# tiva-c.net
KiCad netlist of a schematic drawn in EAGLE
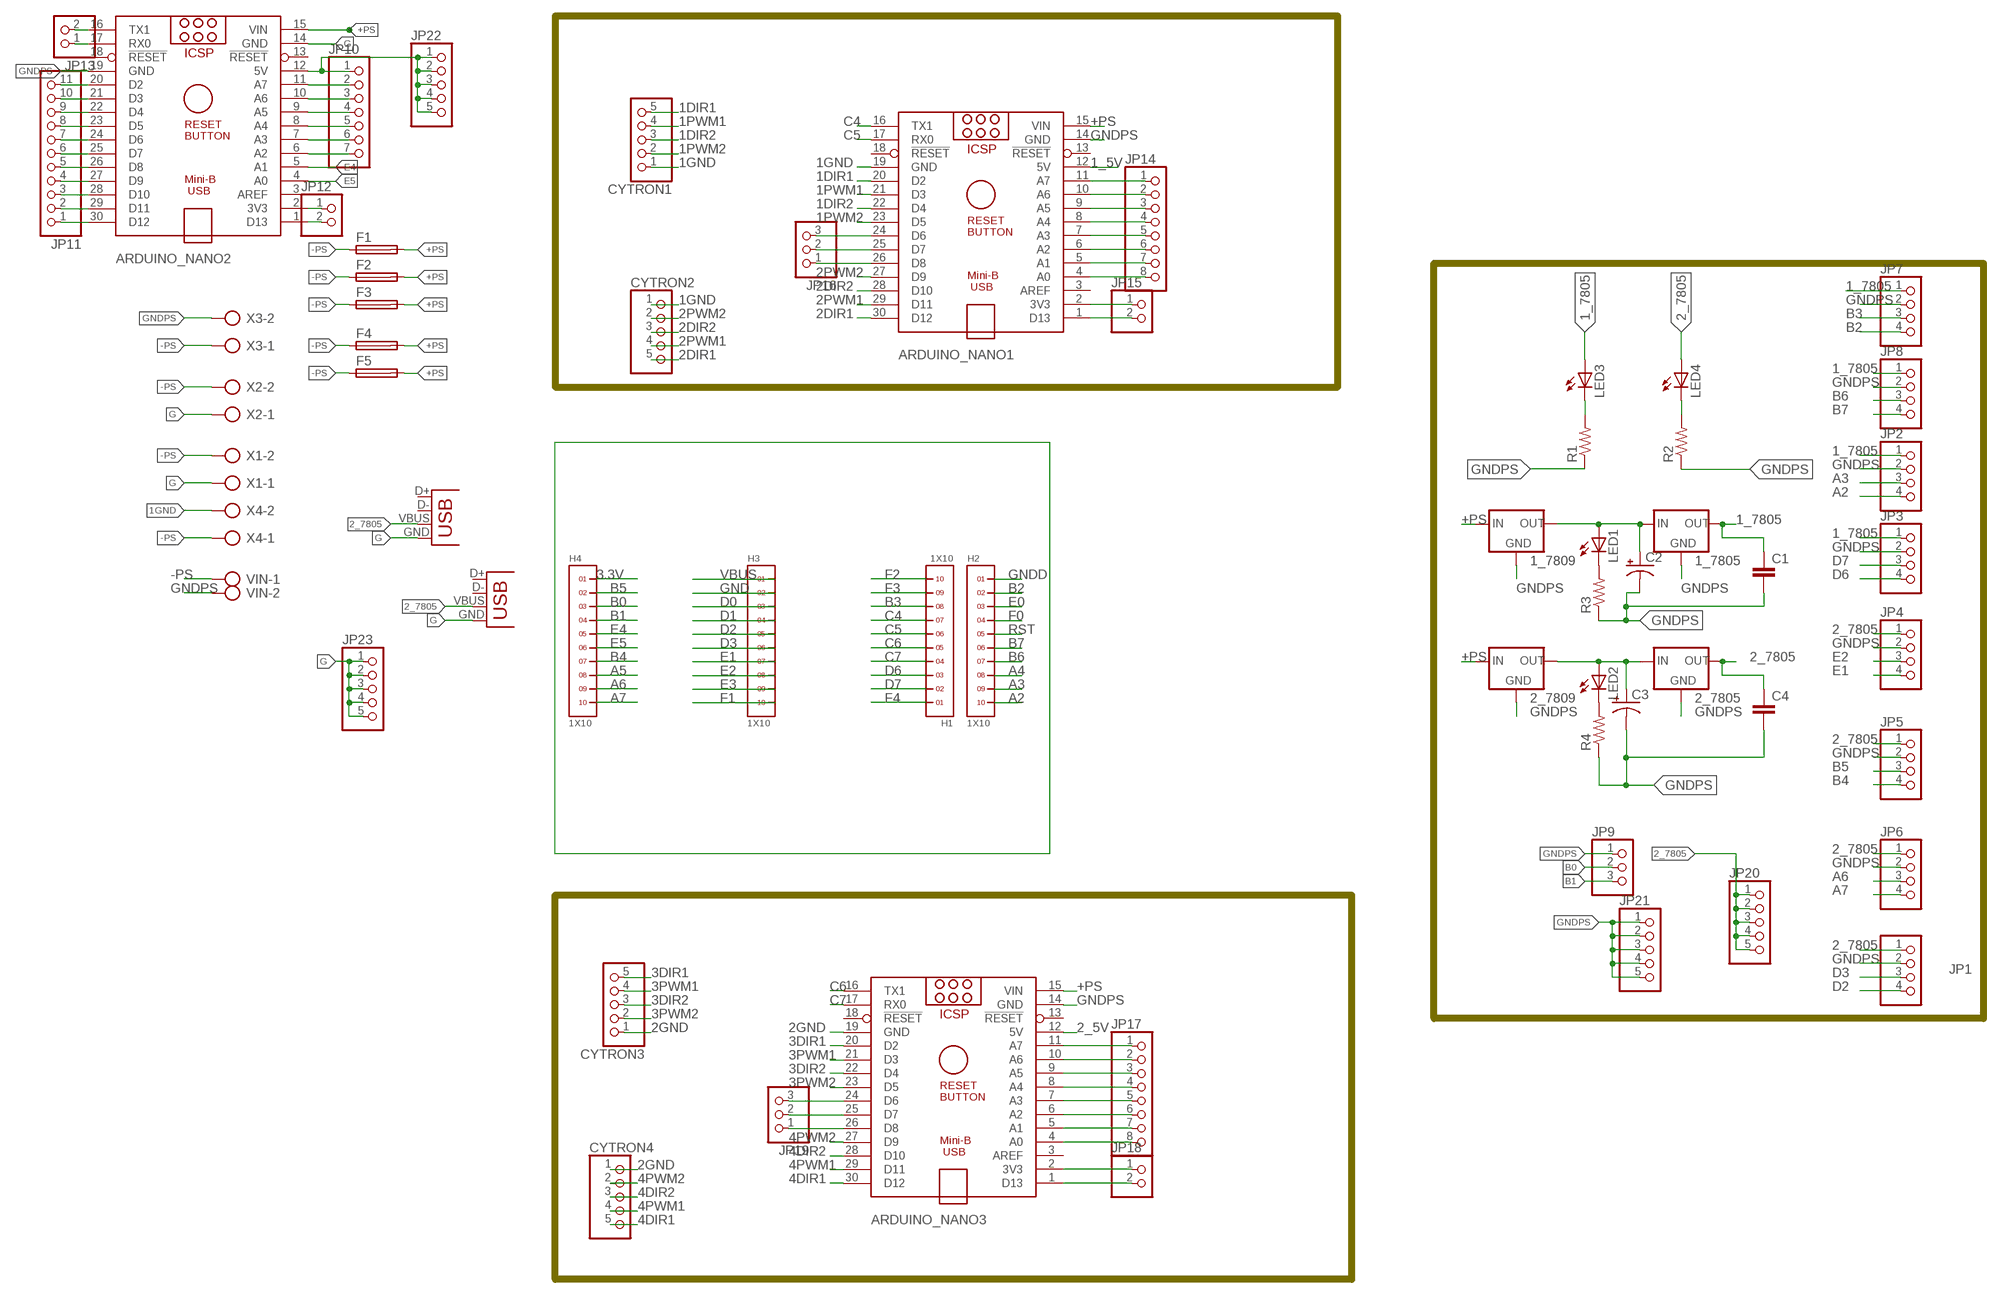
[diagram p0: schematic, sheet 1]

(export (version "E")
  (design (tool "Eeschema 10.0.6"))
  (components
    (comp (ref "1_7805")
      (value "78XXS")
      (footprint "eagle-import:78XXS")
      (libsource (lib "eagle-import") (part "78XXS"))
    )
    (comp (ref "1_7809")
      (value "78XXS")
      (footprint "eagle-import:78XXS")
      (libsource (lib "eagle-import") (part "78XXS"))
    )
    (comp (ref "2_7805")
      (value "78XXS")
      (footprint "eagle-import:78XXS")
      (libsource (lib "eagle-import") (part "78XXS"))
    )
    (comp (ref "2_7809")
      (value "78XXS")
      (footprint "eagle-import:78XXS")
      (libsource (lib "eagle-import") (part "78XXS"))
    )
    (comp (ref "ARDUINO_NANO1")
      (value "ARDUINO_NANO")
      (footprint "eagle-import:ARDUINO_NANO")
      (libsource (lib "eagle-import") (part "ARDUINO_NANO"))
    )
    (comp (ref "ARDUINO_NANO2")
      (value "ARDUINO_NANO")
      (footprint "eagle-import:ARDUINO_NANO")
      (libsource (lib "eagle-import") (part "ARDUINO_NANO"))
    )
    (comp (ref "ARDUINO_NANO3")
      (value "ARDUINO_NANO")
      (footprint "eagle-import:ARDUINO_NANO")
      (libsource (lib "eagle-import") (part "ARDUINO_NANO"))
    )
    (comp (ref "C1")
      (value "C-EU025-030X050")
      (footprint "eagle-import:C025-030X050")
      (libsource (lib "eagle-import") (part "C-EU025-030X050"))
    )
    (comp (ref "C2")
      (value "CPOL-USE2.5-5")
      (footprint "eagle-import:E2,5-5")
      (libsource (lib "eagle-import") (part "CPOL-USE2.5-5"))
    )
    (comp (ref "C3")
      (value "CPOL-USE2.5-5")
      (footprint "eagle-import:E2,5-5")
      (libsource (lib "eagle-import") (part "CPOL-USE2.5-5"))
    )
    (comp (ref "C4")
      (value "C-EU025-030X050")
      (footprint "eagle-import:C025-030X050")
      (libsource (lib "eagle-import") (part "C-EU025-030X050"))
    )
    (comp (ref "CYTRON1")
      (value "PINHD-1X5")
      (footprint "eagle-import:1X05")
      (libsource (lib "eagle-import") (part "PINHD-1X5"))
    )
    (comp (ref "CYTRON2")
      (value "PINHD-1X5")
      (footprint "eagle-import:1X05")
      (libsource (lib "eagle-import") (part "PINHD-1X5"))
    )
    (comp (ref "CYTRON3")
      (value "PINHD-1X5")
      (footprint "eagle-import:1X05")
      (libsource (lib "eagle-import") (part "PINHD-1X5"))
    )
    (comp (ref "CYTRON4")
      (value "PINHD-1X5")
      (footprint "eagle-import:1X05")
      (libsource (lib "eagle-import") (part "PINHD-1X5"))
    )
    (comp (ref "F1")
      (value "SH22,5A")
      (footprint "eagle-import:SH22,5A")
      (fields (field (name "MPN") "0031.7701.11"))
      (libsource (lib "eagle-import") (part "SH22,5A"))
    )
    (comp (ref "F2")
      (value "SH22,5A")
      (footprint "eagle-import:SH22,5A")
      (fields (field (name "MPN") "0031.7701.11"))
      (libsource (lib "eagle-import") (part "SH22,5A"))
    )
    (comp (ref "F3")
      (value "SH22,5A")
      (footprint "eagle-import:SH22,5A")
      (fields (field (name "MPN") "0031.7701.11"))
      (libsource (lib "eagle-import") (part "SH22,5A"))
    )
    (comp (ref "F4")
      (value "SH22,5A")
      (footprint "eagle-import:SH22,5A")
      (fields (field (name "MPN") "0031.7701.11"))
      (libsource (lib "eagle-import") (part "SH22,5A"))
    )
    (comp (ref "F5")
      (value "SH22,5A")
      (footprint "eagle-import:SH22,5A")
      (fields (field (name "MPN") "0031.7701.11"))
      (libsource (lib "eagle-import") (part "SH22,5A"))
    )
    (comp (ref "H1")
      (value "1X10")
      (footprint "eagle-import:1X10")
      (libsource (lib "eagle-import") (part "1X10"))
    )
    (comp (ref "H2")
      (value "1X10")
      (footprint "eagle-import:1X10")
      (libsource (lib "eagle-import") (part "1X10"))
    )
    (comp (ref "H3")
      (value "1X10")
      (footprint "eagle-import:1X10")
      (libsource (lib "eagle-import") (part "1X10"))
    )
    (comp (ref "H4")
      (value "1X10")
      (footprint "eagle-import:1X10")
      (libsource (lib "eagle-import") (part "1X10"))
    )
    (comp (ref "JP1")
      (value "PINHD-1X4")
      (footprint "eagle-import:1X04")
      (libsource (lib "eagle-import") (part "PINHD-1X4"))
    )
    (comp (ref "JP2")
      (value "PINHD-1X4")
      (footprint "eagle-import:1X04")
      (libsource (lib "eagle-import") (part "PINHD-1X4"))
    )
    (comp (ref "JP3")
      (value "PINHD-1X4")
      (footprint "eagle-import:1X04")
      (libsource (lib "eagle-import") (part "PINHD-1X4"))
    )
    (comp (ref "JP4")
      (value "PINHD-1X4")
      (footprint "eagle-import:1X04")
      (libsource (lib "eagle-import") (part "PINHD-1X4"))
    )
    (comp (ref "JP5")
      (value "PINHD-1X4")
      (footprint "eagle-import:1X04")
      (libsource (lib "eagle-import") (part "PINHD-1X4"))
    )
    (comp (ref "JP6")
      (value "PINHD-1X4")
      (footprint "eagle-import:1X04")
      (libsource (lib "eagle-import") (part "PINHD-1X4"))
    )
    (comp (ref "JP7")
      (value "PINHD-1X4")
      (footprint "eagle-import:1X04")
      (libsource (lib "eagle-import") (part "PINHD-1X4"))
    )
    (comp (ref "JP8")
      (value "PINHD-1X4")
      (footprint "eagle-import:1X04")
      (libsource (lib "eagle-import") (part "PINHD-1X4"))
    )
    (comp (ref "JP9")
      (value "PINHD-1X3")
      (footprint "eagle-import:1X03")
      (libsource (lib "eagle-import") (part "PINHD-1X3"))
    )
    (comp (ref "JP10")
      (value "PINHD-1X7")
      (footprint "eagle-import:1X07")
      (libsource (lib "eagle-import") (part "PINHD-1X7"))
    )
    (comp (ref "JP11")
      (value "PINHD-1X11")
      (footprint "eagle-import:1X11")
      (libsource (lib "eagle-import") (part "PINHD-1X11"))
    )
    (comp (ref "JP12")
      (value "PINHD-1X2")
      (footprint "eagle-import:1X02")
      (libsource (lib "eagle-import") (part "PINHD-1X2"))
    )
    (comp (ref "JP13")
      (value "PINHD-1X2")
      (footprint "eagle-import:1X02")
      (libsource (lib "eagle-import") (part "PINHD-1X2"))
    )
    (comp (ref "JP14")
      (value "PINHD-1X8")
      (footprint "eagle-import:1X08")
      (libsource (lib "eagle-import") (part "PINHD-1X8"))
    )
    (comp (ref "JP15")
      (value "PINHD-1X2")
      (footprint "eagle-import:1X02")
      (libsource (lib "eagle-import") (part "PINHD-1X2"))
    )
    (comp (ref "JP16")
      (value "PINHD-1X3")
      (footprint "eagle-import:1X03")
      (libsource (lib "eagle-import") (part "PINHD-1X3"))
    )
    (comp (ref "JP17")
      (value "PINHD-1X8")
      (footprint "eagle-import:1X08")
      (libsource (lib "eagle-import") (part "PINHD-1X8"))
    )
    (comp (ref "JP18")
      (value "PINHD-1X2")
      (footprint "eagle-import:1X02")
      (libsource (lib "eagle-import") (part "PINHD-1X2"))
    )
    (comp (ref "JP19")
      (value "PINHD-1X3")
      (footprint "eagle-import:1X03")
      (libsource (lib "eagle-import") (part "PINHD-1X3"))
    )
    (comp (ref "JP20")
      (value "PINHD-1X5")
      (footprint "eagle-import:1X05")
      (libsource (lib "eagle-import") (part "pinhead_325_PINHD-1X5"))
    )
    (comp (ref "JP21")
      (value "PINHD-1X5")
      (footprint "eagle-import:1X05")
      (libsource (lib "eagle-import") (part "pinhead_325_PINHD-1X5"))
    )
    (comp (ref "JP22")
      (value "PINHD-1X5")
      (footprint "eagle-import:1X05")
      (libsource (lib "eagle-import") (part "pinhead_325_PINHD-1X5"))
    )
    (comp (ref "JP23")
      (value "PINHD-1X5")
      (footprint "eagle-import:1X05")
      (libsource (lib "eagle-import") (part "pinhead_325_PINHD-1X5"))
    )
    (comp (ref "LED1")
      (value "LED5MM")
      (footprint "eagle-import:LED5MM")
      (libsource (lib "eagle-import") (part "LED5MM"))
    )
    (comp (ref "LED2")
      (value "LED5MM")
      (footprint "eagle-import:LED5MM")
      (libsource (lib "eagle-import") (part "LED5MM"))
    )
    (comp (ref "LED3")
      (value "LED5MM")
      (footprint "eagle-import:LED5MM")
      (libsource (lib "eagle-import") (part "LED5MM"))
    )
    (comp (ref "LED4")
      (value "LED5MM")
      (footprint "eagle-import:LED5MM")
      (libsource (lib "eagle-import") (part "LED5MM"))
    )
    (comp (ref "R1")
      (value "R-US_0204/5")
      (footprint "eagle-import:0204_5")
      (libsource (lib "eagle-import") (part "R-US_0204/5"))
    )
    (comp (ref "R2")
      (value "R-US_0204/5")
      (footprint "eagle-import:0204_5")
      (libsource (lib "eagle-import") (part "R-US_0204/5"))
    )
    (comp (ref "R3")
      (value "R-US_0204/5")
      (footprint "eagle-import:0204_5")
      (libsource (lib "eagle-import") (part "R-US_0204/5"))
    )
    (comp (ref "R4")
      (value "R-US_0204/5")
      (footprint "eagle-import:0204_5")
      (libsource (lib "eagle-import") (part "R-US_0204/5"))
    )
    (comp (ref "VIN")
      (value "AK300/2")
      (footprint "eagle-import:AK300_2")
      (libsource (lib "eagle-import") (part "AK300/2"))
    )
    (comp (ref "X1")
      (value "AK300/2")
      (footprint "eagle-import:AK300_2")
      (libsource (lib "eagle-import") (part "con-ptr500_181_AK300/2"))
    )
    (comp (ref "X2")
      (value "AK300/2")
      (footprint "eagle-import:AK300_2")
      (libsource (lib "eagle-import") (part "con-ptr500_181_AK300/2"))
    )
    (comp (ref "X3")
      (value "AK300/2")
      (footprint "eagle-import:AK300_2")
      (libsource (lib "eagle-import") (part "con-ptr500_181_AK300/2"))
    )
    (comp (ref "X4")
      (value "AK300/2")
      (footprint "eagle-import:AK300_2")
      (libsource (lib "eagle-import") (part "con-ptr500_181_AK300/2"))
    )
    (comp (ref "X5")
      (value "USB-A-H")
      (footprint "eagle-import:USB-A-H")
      (libsource (lib "eagle-import") (part "USB-A-H"))
    )
    (comp (ref "X6")
      (value "USB-A-H")
      (footprint "eagle-import:USB-A-H")
      (libsource (lib "eagle-import") (part "USB-A-H"))
    )
  )
  (nets
    (net (code "1") (name "+PS") (class "Default")
      (node (ref "1_7809") (pin "IN") (pinfunction "IN_IN") (pintype "input"))
      (node (ref "2_7809") (pin "IN") (pinfunction "IN_IN") (pintype "input"))
      (node (ref "ARDUINO_NANO1") (pin "15") (pinfunction "VIN_15") (pintype "power_in"))
      (node (ref "ARDUINO_NANO2") (pin "15") (pinfunction "VIN_15") (pintype "power_in"))
      (node (ref "ARDUINO_NANO3") (pin "15") (pinfunction "VIN_15") (pintype "power_in"))
      (node (ref "F1") (pin "2") (pinfunction "2_2") (pintype "passive"))
      (node (ref "F2") (pin "2") (pinfunction "2_2") (pintype "passive"))
      (node (ref "F3") (pin "2") (pinfunction "2_2") (pintype "passive"))
      (node (ref "F4") (pin "2") (pinfunction "2_2") (pintype "passive"))
      (node (ref "F5") (pin "2") (pinfunction "2_2") (pintype "passive"))
    )
    (net (code "2") (name "-PS") (class "Default")
      (node (ref "F1") (pin "1") (pinfunction "1_1") (pintype "passive"))
      (node (ref "F2") (pin "1") (pinfunction "1_1") (pintype "passive"))
      (node (ref "F3") (pin "1") (pinfunction "1_1") (pintype "passive"))
      (node (ref "F4") (pin "1") (pinfunction "1_1") (pintype "passive"))
      (node (ref "F5") (pin "1") (pinfunction "1_1") (pintype "passive"))
      (node (ref "VIN") (pin "1") (pinfunction "KL_1") (pintype "passive"))
      (node (ref "X1") (pin "2") (pinfunction "KL_2") (pintype "passive"))
      (node (ref "X2") (pin "2") (pinfunction "KL_2") (pintype "passive"))
      (node (ref "X3") (pin "1") (pinfunction "KL_1") (pintype "passive"))
      (node (ref "X4") (pin "1") (pinfunction "KL_1") (pintype "passive"))
    )
    (net (code "3") (name "/1DIR1") (class "Default")
      (node (ref "ARDUINO_NANO1") (pin "20") (pinfunction "D2_20") (pintype "bidirectional"))
      (node (ref "CYTRON1") (pin "5") (pinfunction "5_5") (pintype "passive"))
    )
    (net (code "4") (name "/1DIR2") (class "Default")
      (node (ref "ARDUINO_NANO1") (pin "22") (pinfunction "D4_22") (pintype "bidirectional"))
      (node (ref "CYTRON1") (pin "3") (pinfunction "3_3") (pintype "passive"))
    )
    (net (code "5") (name "/1PWM1") (class "Default")
      (node (ref "ARDUINO_NANO1") (pin "21") (pinfunction "D3_21") (pintype "bidirectional"))
      (node (ref "CYTRON1") (pin "4") (pinfunction "4_4") (pintype "passive"))
    )
    (net (code "6") (name "/1PWM2") (class "Default")
      (node (ref "ARDUINO_NANO1") (pin "23") (pinfunction "D5_23") (pintype "bidirectional"))
      (node (ref "CYTRON1") (pin "2") (pinfunction "2_2") (pintype "passive"))
    )
    (net (code "7") (name "/1_5V") (class "Default")
      (node (ref "ARDUINO_NANO1") (pin "12") (pinfunction "5V_12") (pintype "power_in"))
    )
    (net (code "8") (name "/2DIR1") (class "Default")
      (node (ref "ARDUINO_NANO1") (pin "30") (pinfunction "D12_30") (pintype "bidirectional"))
      (node (ref "CYTRON2") (pin "5") (pinfunction "5_5") (pintype "passive"))
    )
    (net (code "9") (name "/2DIR2") (class "Default")
      (node (ref "ARDUINO_NANO1") (pin "28") (pinfunction "D10_28") (pintype "bidirectional"))
      (node (ref "CYTRON2") (pin "3") (pinfunction "3_3") (pintype "passive"))
    )
    (net (code "10") (name "/2GND") (class "Default")
      (node (ref "ARDUINO_NANO3") (pin "19") (pinfunction "GND_19") (pintype "power_in"))
      (node (ref "CYTRON3") (pin "1") (pinfunction "1_1") (pintype "passive"))
      (node (ref "CYTRON4") (pin "1") (pinfunction "1_1") (pintype "passive"))
    )
    (net (code "11") (name "/2PWM1") (class "Default")
      (node (ref "ARDUINO_NANO1") (pin "29") (pinfunction "D11_29") (pintype "bidirectional"))
      (node (ref "CYTRON2") (pin "4") (pinfunction "4_4") (pintype "passive"))
    )
    (net (code "12") (name "/2PWM2") (class "Default")
      (node (ref "ARDUINO_NANO1") (pin "27") (pinfunction "D9_27") (pintype "bidirectional"))
      (node (ref "CYTRON2") (pin "2") (pinfunction "2_2") (pintype "passive"))
    )
    (net (code "13") (name "/2_5V") (class "Default")
      (node (ref "ARDUINO_NANO3") (pin "12") (pinfunction "5V_12") (pintype "power_in"))
    )
    (net (code "14") (name "/3.3V") (class "Default")
      (node (ref "H4") (pin "1") (pinfunction "1_1") (pintype "bidirectional"))
    )
    (net (code "15") (name "/3DIR1") (class "Default")
      (node (ref "ARDUINO_NANO3") (pin "20") (pinfunction "D2_20") (pintype "bidirectional"))
      (node (ref "CYTRON3") (pin "5") (pinfunction "5_5") (pintype "passive"))
    )
    (net (code "16") (name "/3DIR2") (class "Default")
      (node (ref "ARDUINO_NANO3") (pin "22") (pinfunction "D4_22") (pintype "bidirectional"))
      (node (ref "CYTRON3") (pin "3") (pinfunction "3_3") (pintype "passive"))
    )
    (net (code "17") (name "/3PWM1") (class "Default")
      (node (ref "ARDUINO_NANO3") (pin "21") (pinfunction "D3_21") (pintype "bidirectional"))
      (node (ref "CYTRON3") (pin "4") (pinfunction "4_4") (pintype "passive"))
    )
    (net (code "18") (name "/3PWM2") (class "Default")
      (node (ref "ARDUINO_NANO3") (pin "23") (pinfunction "D5_23") (pintype "bidirectional"))
      (node (ref "CYTRON3") (pin "2") (pinfunction "2_2") (pintype "passive"))
    )
    (net (code "19") (name "/4DIR1") (class "Default")
      (node (ref "ARDUINO_NANO3") (pin "30") (pinfunction "D12_30") (pintype "bidirectional"))
      (node (ref "CYTRON4") (pin "5") (pinfunction "5_5") (pintype "passive"))
    )
    (net (code "20") (name "/4DIR2") (class "Default")
      (node (ref "ARDUINO_NANO3") (pin "28") (pinfunction "D10_28") (pintype "bidirectional"))
      (node (ref "CYTRON4") (pin "3") (pinfunction "3_3") (pintype "passive"))
    )
    (net (code "21") (name "/4PWM1") (class "Default")
      (node (ref "ARDUINO_NANO3") (pin "29") (pinfunction "D11_29") (pintype "bidirectional"))
      (node (ref "CYTRON4") (pin "4") (pinfunction "4_4") (pintype "passive"))
    )
    (net (code "22") (name "/4PWM2") (class "Default")
      (node (ref "ARDUINO_NANO3") (pin "27") (pinfunction "D9_27") (pintype "bidirectional"))
      (node (ref "CYTRON4") (pin "2") (pinfunction "2_2") (pintype "passive"))
    )
    (net (code "23") (name "/A2") (class "Default")
      (node (ref "H2") (pin "10") (pinfunction "10_10") (pintype "bidirectional"))
      (node (ref "JP2") (pin "4") (pinfunction "4_4") (pintype "passive"))
    )
    (net (code "24") (name "/A3") (class "Default")
      (node (ref "H2") (pin "9") (pinfunction "9_9") (pintype "bidirectional"))
      (node (ref "JP2") (pin "3") (pinfunction "3_3") (pintype "passive"))
    )
    (net (code "25") (name "/A4") (class "Default")
      (node (ref "H2") (pin "8") (pinfunction "8_8") (pintype "bidirectional"))
    )
    (net (code "26") (name "/A5") (class "Default")
      (node (ref "H4") (pin "8") (pinfunction "8_8") (pintype "bidirectional"))
    )
    (net (code "27") (name "/A6") (class "Default")
      (node (ref "H4") (pin "9") (pinfunction "9_9") (pintype "bidirectional"))
      (node (ref "JP6") (pin "3") (pinfunction "3_3") (pintype "passive"))
    )
    (net (code "28") (name "/A7") (class "Default")
      (node (ref "H4") (pin "10") (pinfunction "10_10") (pintype "bidirectional"))
      (node (ref "JP6") (pin "4") (pinfunction "4_4") (pintype "passive"))
    )
    (net (code "29") (name "/B2") (class "Default")
      (node (ref "H2") (pin "2") (pinfunction "2_2") (pintype "bidirectional"))
      (node (ref "JP7") (pin "4") (pinfunction "4_4") (pintype "passive"))
    )
    (net (code "30") (name "/B3") (class "Default")
      (node (ref "H1") (pin "8") (pinfunction "8_8") (pintype "bidirectional"))
      (node (ref "JP7") (pin "3") (pinfunction "3_3") (pintype "passive"))
    )
    (net (code "31") (name "/B4") (class "Default")
      (node (ref "H4") (pin "7") (pinfunction "7_7") (pintype "bidirectional"))
      (node (ref "JP5") (pin "4") (pinfunction "4_4") (pintype "passive"))
    )
    (net (code "32") (name "/B5") (class "Default")
      (node (ref "H4") (pin "2") (pinfunction "2_2") (pintype "bidirectional"))
      (node (ref "JP5") (pin "3") (pinfunction "3_3") (pintype "passive"))
    )
    (net (code "33") (name "/B6") (class "Default")
      (node (ref "H2") (pin "7") (pinfunction "7_7") (pintype "bidirectional"))
      (node (ref "JP8") (pin "3") (pinfunction "3_3") (pintype "passive"))
    )
    (net (code "34") (name "/B7") (class "Default")
      (node (ref "H2") (pin "6") (pinfunction "6_6") (pintype "bidirectional"))
      (node (ref "JP8") (pin "4") (pinfunction "4_4") (pintype "passive"))
    )
    (net (code "35") (name "/C4") (class "Default")
      (node (ref "ARDUINO_NANO1") (pin "16") (pinfunction "TX1_16") (pintype "bidirectional"))
      (node (ref "H1") (pin "7") (pinfunction "7_7") (pintype "bidirectional"))
    )
    (net (code "36") (name "/C5") (class "Default")
      (node (ref "ARDUINO_NANO1") (pin "17") (pinfunction "RX0_17") (pintype "bidirectional"))
      (node (ref "H1") (pin "6") (pinfunction "6_6") (pintype "bidirectional"))
    )
    (net (code "37") (name "/C6") (class "Default")
      (node (ref "ARDUINO_NANO3") (pin "16") (pinfunction "TX1_16") (pintype "bidirectional"))
      (node (ref "H1") (pin "5") (pinfunction "5_5") (pintype "bidirectional"))
    )
    (net (code "38") (name "/C7") (class "Default")
      (node (ref "ARDUINO_NANO3") (pin "17") (pinfunction "RX0_17") (pintype "bidirectional"))
      (node (ref "H1") (pin "4") (pinfunction "4_4") (pintype "bidirectional"))
    )
    (net (code "39") (name "/D0") (class "Default")
      (node (ref "H3") (pin "3") (pinfunction "3_3") (pintype "bidirectional"))
    )
    (net (code "40") (name "/D1") (class "Default")
      (node (ref "H3") (pin "4") (pinfunction "4_4") (pintype "bidirectional"))
    )
    (net (code "41") (name "/D2") (class "Default")
      (node (ref "H3") (pin "5") (pinfunction "5_5") (pintype "bidirectional"))
      (node (ref "JP1") (pin "4") (pinfunction "4_4") (pintype "passive"))
    )
    (net (code "42") (name "/D3") (class "Default")
      (node (ref "H3") (pin "6") (pinfunction "6_6") (pintype "bidirectional"))
      (node (ref "JP1") (pin "3") (pinfunction "3_3") (pintype "passive"))
    )
    (net (code "43") (name "/D6") (class "Default")
      (node (ref "H1") (pin "3") (pinfunction "3_3") (pintype "bidirectional"))
      (node (ref "JP3") (pin "4") (pinfunction "4_4") (pintype "passive"))
    )
    (net (code "44") (name "/D7") (class "Default")
      (node (ref "H1") (pin "2") (pinfunction "2_2") (pintype "bidirectional"))
      (node (ref "JP3") (pin "3") (pinfunction "3_3") (pintype "passive"))
    )
    (net (code "45") (name "/E0") (class "Default")
      (node (ref "H2") (pin "3") (pinfunction "3_3") (pintype "bidirectional"))
    )
    (net (code "46") (name "/E1") (class "Default")
      (node (ref "H3") (pin "7") (pinfunction "7_7") (pintype "bidirectional"))
      (node (ref "JP4") (pin "4") (pinfunction "4_4") (pintype "passive"))
    )
    (net (code "47") (name "/E2") (class "Default")
      (node (ref "H3") (pin "8") (pinfunction "8_8") (pintype "bidirectional"))
      (node (ref "JP4") (pin "3") (pinfunction "3_3") (pintype "passive"))
    )
    (net (code "48") (name "/E3") (class "Default")
      (node (ref "H3") (pin "9") (pinfunction "9_9") (pintype "bidirectional"))
    )
    (net (code "49") (name "/F0") (class "Default")
      (node (ref "H2") (pin "4") (pinfunction "4_4") (pintype "bidirectional"))
    )
    (net (code "50") (name "/F1") (class "Default")
      (node (ref "H3") (pin "10") (pinfunction "10_10") (pintype "bidirectional"))
    )
    (net (code "51") (name "/F2") (class "Default")
      (node (ref "H1") (pin "10") (pinfunction "10_10") (pintype "bidirectional"))
    )
    (net (code "52") (name "/F3") (class "Default")
      (node (ref "H1") (pin "9") (pinfunction "9_9") (pintype "bidirectional"))
    )
    (net (code "53") (name "/F4") (class "Default")
      (node (ref "H1") (pin "1") (pinfunction "1_1") (pintype "bidirectional"))
    )
    (net (code "54") (name "/GND") (class "Default")
      (node (ref "H3") (pin "2") (pinfunction "2_2") (pintype "bidirectional"))
    )
    (net (code "55") (name "/GNDD") (class "Default")
      (node (ref "H2") (pin "1") (pinfunction "1_1") (pintype "bidirectional"))
    )
    (net (code "56") (name "/RST") (class "Default")
      (node (ref "H2") (pin "5") (pinfunction "5_5") (pintype "bidirectional"))
    )
    (net (code "57") (name "/VBUS") (class "Default")
      (node (ref "H3") (pin "1") (pinfunction "1_1") (pintype "bidirectional"))
    )
    (net (code "58") (name "1GND") (class "Default")
      (node (ref "ARDUINO_NANO1") (pin "19") (pinfunction "GND_19") (pintype "power_in"))
      (node (ref "CYTRON1") (pin "1") (pinfunction "1_1") (pintype "passive"))
      (node (ref "CYTRON2") (pin "1") (pinfunction "1_1") (pintype "passive"))
      (node (ref "X4") (pin "2") (pinfunction "KL_2") (pintype "passive"))
    )
    (net (code "59") (name "1_7805") (class "Default")
      (node (ref "1_7805") (pin "OUT") (pinfunction "OUT_OUT") (pintype "passive"))
      (node (ref "C1") (pin "1") (pinfunction "1_1") (pintype "passive"))
      (node (ref "JP2") (pin "1") (pinfunction "1_1") (pintype "passive"))
      (node (ref "JP3") (pin "1") (pinfunction "1_1") (pintype "passive"))
      (node (ref "JP7") (pin "1") (pinfunction "1_1") (pintype "passive"))
      (node (ref "JP8") (pin "1") (pinfunction "1_1") (pintype "passive"))
      (node (ref "LED3") (pin "A") (pinfunction "A_A") (pintype "passive"))
    )
    (net (code "60") (name "2_7805") (class "Default")
      (node (ref "2_7805") (pin "OUT") (pinfunction "OUT_OUT") (pintype "passive"))
      (node (ref "C4") (pin "1") (pinfunction "1_1") (pintype "passive"))
      (node (ref "JP1") (pin "1") (pinfunction "1_1") (pintype "passive"))
      (node (ref "JP20") (pin "1") (pinfunction "1_1") (pintype "passive"))
      (node (ref "JP20") (pin "2") (pinfunction "2_2") (pintype "passive"))
      (node (ref "JP20") (pin "3") (pinfunction "3_3") (pintype "passive"))
      (node (ref "JP20") (pin "4") (pinfunction "4_4") (pintype "passive"))
      (node (ref "JP20") (pin "5") (pinfunction "5_5") (pintype "passive"))
      (node (ref "JP4") (pin "1") (pinfunction "1_1") (pintype "passive"))
      (node (ref "JP5") (pin "1") (pinfunction "1_1") (pintype "passive"))
      (node (ref "JP6") (pin "1") (pinfunction "1_1") (pintype "passive"))
      (node (ref "LED4") (pin "A") (pinfunction "A_A") (pintype "passive"))
      (node (ref "X5") (pin "VBUS") (pinfunction "VBUS_VBUS") (pintype "bidirectional"))
      (node (ref "X6") (pin "VBUS") (pinfunction "VBUS_VBUS") (pintype "bidirectional"))
    )
    (net (code "61") (name "B0") (class "Default")
      (node (ref "H4") (pin "3") (pinfunction "3_3") (pintype "bidirectional"))
      (node (ref "JP9") (pin "2") (pinfunction "2_2") (pintype "passive"))
    )
    (net (code "62") (name "B1") (class "Default")
      (node (ref "H4") (pin "4") (pinfunction "4_4") (pintype "bidirectional"))
      (node (ref "JP9") (pin "3") (pinfunction "3_3") (pintype "passive"))
    )
    (net (code "63") (name "E4") (class "Default")
      (node (ref "ARDUINO_NANO2") (pin "5") (pinfunction "A1_5") (pintype "bidirectional"))
      (node (ref "H4") (pin "5") (pinfunction "5_5") (pintype "bidirectional"))
    )
    (net (code "64") (name "E5") (class "Default")
      (node (ref "ARDUINO_NANO2") (pin "4") (pinfunction "A0_4") (pintype "bidirectional"))
      (node (ref "H4") (pin "6") (pinfunction "6_6") (pintype "bidirectional"))
    )
    (net (code "65") (name "G") (class "Default")
      (node (ref "ARDUINO_NANO2") (pin "14") (pinfunction "GND_14") (pintype "power_in"))
      (node (ref "JP23") (pin "1") (pinfunction "1_1") (pintype "passive"))
      (node (ref "JP23") (pin "2") (pinfunction "2_2") (pintype "passive"))
      (node (ref "JP23") (pin "3") (pinfunction "3_3") (pintype "passive"))
      (node (ref "JP23") (pin "4") (pinfunction "4_4") (pintype "passive"))
      (node (ref "JP23") (pin "5") (pinfunction "5_5") (pintype "passive"))
      (node (ref "X1") (pin "1") (pinfunction "KL_1") (pintype "passive"))
      (node (ref "X2") (pin "1") (pinfunction "KL_1") (pintype "passive"))
      (node (ref "X5") (pin "GND") (pinfunction "GND_GND") (pintype "bidirectional"))
      (node (ref "X6") (pin "GND") (pinfunction "GND_GND") (pintype "bidirectional"))
    )
    (net (code "66") (name "GNDPS") (class "Default")
      (node (ref "1_7805") (pin "GND") (pinfunction "GND_GND") (pintype "input"))
      (node (ref "1_7809") (pin "GND") (pinfunction "GND_GND") (pintype "input"))
      (node (ref "2_7805") (pin "GND") (pinfunction "GND_GND") (pintype "input"))
      (node (ref "2_7809") (pin "GND") (pinfunction "GND_GND") (pintype "input"))
      (node (ref "ARDUINO_NANO1") (pin "14") (pinfunction "GND_14") (pintype "power_in"))
      (node (ref "ARDUINO_NANO2") (pin "19") (pinfunction "GND_19") (pintype "power_in"))
      (node (ref "ARDUINO_NANO3") (pin "14") (pinfunction "GND_14") (pintype "power_in"))
      (node (ref "C1") (pin "2") (pinfunction "2_2") (pintype "passive"))
      (node (ref "C2") (pin "-") (pinfunction "-_-") (pintype "passive"))
      (node (ref "C3") (pin "-") (pinfunction "-_-") (pintype "passive"))
      (node (ref "C4") (pin "2") (pinfunction "2_2") (pintype "passive"))
      (node (ref "JP1") (pin "2") (pinfunction "2_2") (pintype "passive"))
      (node (ref "JP2") (pin "2") (pinfunction "2_2") (pintype "passive"))
      (node (ref "JP21") (pin "1") (pinfunction "1_1") (pintype "passive"))
      (node (ref "JP21") (pin "2") (pinfunction "2_2") (pintype "passive"))
      (node (ref "JP21") (pin "3") (pinfunction "3_3") (pintype "passive"))
      (node (ref "JP21") (pin "4") (pinfunction "4_4") (pintype "passive"))
      (node (ref "JP21") (pin "5") (pinfunction "5_5") (pintype "passive"))
      (node (ref "JP3") (pin "2") (pinfunction "2_2") (pintype "passive"))
      (node (ref "JP4") (pin "2") (pinfunction "2_2") (pintype "passive"))
      (node (ref "JP5") (pin "2") (pinfunction "2_2") (pintype "passive"))
      (node (ref "JP6") (pin "2") (pinfunction "2_2") (pintype "passive"))
      (node (ref "JP7") (pin "2") (pinfunction "2_2") (pintype "passive"))
      (node (ref "JP8") (pin "2") (pinfunction "2_2") (pintype "passive"))
      (node (ref "JP9") (pin "1") (pinfunction "1_1") (pintype "passive"))
      (node (ref "R1") (pin "1") (pinfunction "1_1") (pintype "passive"))
      (node (ref "R2") (pin "1") (pinfunction "1_1") (pintype "passive"))
      (node (ref "R3") (pin "1") (pinfunction "1_1") (pintype "passive"))
      (node (ref "R4") (pin "1") (pinfunction "1_1") (pintype "passive"))
      (node (ref "VIN") (pin "2") (pinfunction "KL_2") (pintype "passive"))
      (node (ref "X3") (pin "2") (pinfunction "KL_2") (pintype "passive"))
    )
    (net (code "67") (name "Net-(1_7805-PadIN)") (class "Default")
      (node (ref "1_7805") (pin "IN") (pinfunction "IN_IN") (pintype "input"))
      (node (ref "1_7809") (pin "OUT") (pinfunction "OUT_OUT") (pintype "passive"))
      (node (ref "C2") (pin "+") (pinfunction "+_+") (pintype "passive"))
      (node (ref "LED1") (pin "A") (pinfunction "A_A") (pintype "passive"))
    )
    (net (code "68") (name "Net-(2_7805-PadIN)") (class "Default")
      (node (ref "2_7805") (pin "IN") (pinfunction "IN_IN") (pintype "input"))
      (node (ref "2_7809") (pin "OUT") (pinfunction "OUT_OUT") (pintype "passive"))
      (node (ref "C3") (pin "+") (pinfunction "+_+") (pintype "passive"))
      (node (ref "LED2") (pin "A") (pinfunction "A_A") (pintype "passive"))
    )
    (net (code "69") (name "Net-(ARDUINO_NANO1-3V3)") (class "Default")
      (node (ref "ARDUINO_NANO1") (pin "2") (pinfunction "3V3_2") (pintype "output"))
      (node (ref "JP15") (pin "1") (pinfunction "1_1") (pintype "passive"))
    )
    (net (code "70") (name "Net-(ARDUINO_NANO1-A0)") (class "Default")
      (node (ref "ARDUINO_NANO1") (pin "4") (pinfunction "A0_4") (pintype "bidirectional"))
      (node (ref "JP14") (pin "8") (pinfunction "8_8") (pintype "passive"))
    )
    (net (code "71") (name "Net-(ARDUINO_NANO1-A1)") (class "Default")
      (node (ref "ARDUINO_NANO1") (pin "5") (pinfunction "A1_5") (pintype "bidirectional"))
      (node (ref "JP14") (pin "7") (pinfunction "7_7") (pintype "passive"))
    )
    (net (code "72") (name "Net-(ARDUINO_NANO1-A2)") (class "Default")
      (node (ref "ARDUINO_NANO1") (pin "6") (pinfunction "A2_6") (pintype "bidirectional"))
      (node (ref "JP14") (pin "6") (pinfunction "6_6") (pintype "passive"))
    )
    (net (code "73") (name "Net-(ARDUINO_NANO1-A3)") (class "Default")
      (node (ref "ARDUINO_NANO1") (pin "7") (pinfunction "A3_7") (pintype "bidirectional"))
      (node (ref "JP14") (pin "5") (pinfunction "5_5") (pintype "passive"))
    )
    (net (code "74") (name "Net-(ARDUINO_NANO1-A4)") (class "Default")
      (node (ref "ARDUINO_NANO1") (pin "8") (pinfunction "A4_8") (pintype "bidirectional"))
      (node (ref "JP14") (pin "4") (pinfunction "4_4") (pintype "passive"))
    )
    (net (code "75") (name "Net-(ARDUINO_NANO1-A5)") (class "Default")
      (node (ref "ARDUINO_NANO1") (pin "9") (pinfunction "A5_9") (pintype "bidirectional"))
      (node (ref "JP14") (pin "3") (pinfunction "3_3") (pintype "passive"))
    )
    (net (code "76") (name "Net-(ARDUINO_NANO1-A6)") (class "Default")
      (node (ref "ARDUINO_NANO1") (pin "10") (pinfunction "A6_10") (pintype "bidirectional"))
      (node (ref "JP14") (pin "2") (pinfunction "2_2") (pintype "passive"))
    )
    (net (code "77") (name "Net-(ARDUINO_NANO1-A7)") (class "Default")
      (node (ref "ARDUINO_NANO1") (pin "11") (pinfunction "A7_11") (pintype "bidirectional"))
      (node (ref "JP14") (pin "1") (pinfunction "1_1") (pintype "passive"))
    )
    (net (code "78") (name "Net-(ARDUINO_NANO1-D6)") (class "Default")
      (node (ref "ARDUINO_NANO1") (pin "24") (pinfunction "D6_24") (pintype "bidirectional"))
      (node (ref "JP16") (pin "3") (pinfunction "3_3") (pintype "passive"))
    )
    (net (code "79") (name "Net-(ARDUINO_NANO1-D7)") (class "Default")
      (node (ref "ARDUINO_NANO1") (pin "25") (pinfunction "D7_25") (pintype "bidirectional"))
      (node (ref "JP16") (pin "2") (pinfunction "2_2") (pintype "passive"))
    )
    (net (code "80") (name "Net-(ARDUINO_NANO1-D8)") (class "Default")
      (node (ref "ARDUINO_NANO1") (pin "26") (pinfunction "D8_26") (pintype "bidirectional"))
      (node (ref "JP16") (pin "1") (pinfunction "1_1") (pintype "passive"))
    )
    (net (code "81") (name "Net-(ARDUINO_NANO1-D13)") (class "Default")
      (node (ref "ARDUINO_NANO1") (pin "1") (pinfunction "D13_1") (pintype "bidirectional"))
      (node (ref "JP15") (pin "2") (pinfunction "2_2") (pintype "passive"))
    )
    (net (code "82") (name "Net-(ARDUINO_NANO2-3V3)") (class "Default")
      (node (ref "ARDUINO_NANO2") (pin "2") (pinfunction "3V3_2") (pintype "output"))
      (node (ref "JP12") (pin "1") (pinfunction "1_1") (pintype "passive"))
    )
    (net (code "83") (name "Net-(ARDUINO_NANO2-5V)") (class "Default")
      (node (ref "ARDUINO_NANO2") (pin "12") (pinfunction "5V_12") (pintype "power_in"))
      (node (ref "JP10") (pin "1") (pinfunction "1_1") (pintype "passive"))
      (node (ref "JP22") (pin "1") (pinfunction "1_1") (pintype "passive"))
      (node (ref "JP22") (pin "2") (pinfunction "2_2") (pintype "passive"))
      (node (ref "JP22") (pin "3") (pinfunction "3_3") (pintype "passive"))
      (node (ref "JP22") (pin "4") (pinfunction "4_4") (pintype "passive"))
      (node (ref "JP22") (pin "5") (pinfunction "5_5") (pintype "passive"))
    )
    (net (code "84") (name "Net-(ARDUINO_NANO2-A2)") (class "Default")
      (node (ref "ARDUINO_NANO2") (pin "6") (pinfunction "A2_6") (pintype "bidirectional"))
      (node (ref "JP10") (pin "7") (pinfunction "7_7") (pintype "passive"))
    )
    (net (code "85") (name "Net-(ARDUINO_NANO2-A3)") (class "Default")
      (node (ref "ARDUINO_NANO2") (pin "7") (pinfunction "A3_7") (pintype "bidirectional"))
      (node (ref "JP10") (pin "6") (pinfunction "6_6") (pintype "passive"))
    )
    (net (code "86") (name "Net-(ARDUINO_NANO2-A4)") (class "Default")
      (node (ref "ARDUINO_NANO2") (pin "8") (pinfunction "A4_8") (pintype "bidirectional"))
      (node (ref "JP10") (pin "5") (pinfunction "5_5") (pintype "passive"))
    )
    (net (code "87") (name "Net-(ARDUINO_NANO2-A5)") (class "Default")
      (node (ref "ARDUINO_NANO2") (pin "9") (pinfunction "A5_9") (pintype "bidirectional"))
      (node (ref "JP10") (pin "4") (pinfunction "4_4") (pintype "passive"))
    )
    (net (code "88") (name "Net-(ARDUINO_NANO2-A6)") (class "Default")
      (node (ref "ARDUINO_NANO2") (pin "10") (pinfunction "A6_10") (pintype "bidirectional"))
      (node (ref "JP10") (pin "3") (pinfunction "3_3") (pintype "passive"))
    )
    (net (code "89") (name "Net-(ARDUINO_NANO2-A7)") (class "Default")
      (node (ref "ARDUINO_NANO2") (pin "11") (pinfunction "A7_11") (pintype "bidirectional"))
      (node (ref "JP10") (pin "2") (pinfunction "2_2") (pintype "passive"))
    )
    (net (code "90") (name "Net-(ARDUINO_NANO2-D2)") (class "Default")
      (node (ref "ARDUINO_NANO2") (pin "20") (pinfunction "D2_20") (pintype "bidirectional"))
      (node (ref "JP11") (pin "11") (pinfunction "11_11") (pintype "passive"))
    )
    (net (code "91") (name "Net-(ARDUINO_NANO2-D3)") (class "Default")
      (node (ref "ARDUINO_NANO2") (pin "21") (pinfunction "D3_21") (pintype "bidirectional"))
      (node (ref "JP11") (pin "10") (pinfunction "10_10") (pintype "passive"))
    )
    (net (code "92") (name "Net-(ARDUINO_NANO2-D4)") (class "Default")
      (node (ref "ARDUINO_NANO2") (pin "22") (pinfunction "D4_22") (pintype "bidirectional"))
      (node (ref "JP11") (pin "9") (pinfunction "9_9") (pintype "passive"))
    )
    (net (code "93") (name "Net-(ARDUINO_NANO2-D5)") (class "Default")
      (node (ref "ARDUINO_NANO2") (pin "23") (pinfunction "D5_23") (pintype "bidirectional"))
      (node (ref "JP11") (pin "8") (pinfunction "8_8") (pintype "passive"))
    )
    (net (code "94") (name "Net-(ARDUINO_NANO2-D6)") (class "Default")
      (node (ref "ARDUINO_NANO2") (pin "24") (pinfunction "D6_24") (pintype "bidirectional"))
      (node (ref "JP11") (pin "7") (pinfunction "7_7") (pintype "passive"))
    )
    (net (code "95") (name "Net-(ARDUINO_NANO2-D7)") (class "Default")
      (node (ref "ARDUINO_NANO2") (pin "25") (pinfunction "D7_25") (pintype "bidirectional"))
      (node (ref "JP11") (pin "6") (pinfunction "6_6") (pintype "passive"))
    )
    (net (code "96") (name "Net-(ARDUINO_NANO2-D8)") (class "Default")
      (node (ref "ARDUINO_NANO2") (pin "26") (pinfunction "D8_26") (pintype "bidirectional"))
      (node (ref "JP11") (pin "5") (pinfunction "5_5") (pintype "passive"))
    )
    (net (code "97") (name "Net-(ARDUINO_NANO2-D9)") (class "Default")
      (node (ref "ARDUINO_NANO2") (pin "27") (pinfunction "D9_27") (pintype "bidirectional"))
      (node (ref "JP11") (pin "4") (pinfunction "4_4") (pintype "passive"))
    )
    (net (code "98") (name "Net-(ARDUINO_NANO2-D10)") (class "Default")
      (node (ref "ARDUINO_NANO2") (pin "28") (pinfunction "D10_28") (pintype "bidirectional"))
      (node (ref "JP11") (pin "3") (pinfunction "3_3") (pintype "passive"))
    )
    (net (code "99") (name "Net-(ARDUINO_NANO2-D11)") (class "Default")
      (node (ref "ARDUINO_NANO2") (pin "29") (pinfunction "D11_29") (pintype "bidirectional"))
      (node (ref "JP11") (pin "2") (pinfunction "2_2") (pintype "passive"))
    )
    (net (code "100") (name "Net-(ARDUINO_NANO2-D12)") (class "Default")
      (node (ref "ARDUINO_NANO2") (pin "30") (pinfunction "D12_30") (pintype "bidirectional"))
      (node (ref "JP11") (pin "1") (pinfunction "1_1") (pintype "passive"))
    )
    (net (code "101") (name "Net-(ARDUINO_NANO2-D13)") (class "Default")
      (node (ref "ARDUINO_NANO2") (pin "1") (pinfunction "D13_1") (pintype "bidirectional"))
      (node (ref "JP12") (pin "2") (pinfunction "2_2") (pintype "passive"))
    )
    (net (code "102") (name "Net-(ARDUINO_NANO2-RX0)") (class "Default")
      (node (ref "ARDUINO_NANO2") (pin "17") (pinfunction "RX0_17") (pintype "bidirectional"))
      (node (ref "JP13") (pin "1") (pinfunction "1_1") (pintype "passive"))
    )
    (net (code "103") (name "Net-(ARDUINO_NANO2-TX1)") (class "Default")
      (node (ref "ARDUINO_NANO2") (pin "16") (pinfunction "TX1_16") (pintype "bidirectional"))
      (node (ref "JP13") (pin "2") (pinfunction "2_2") (pintype "passive"))
    )
    (net (code "104") (name "Net-(ARDUINO_NANO3-3V3)") (class "Default")
      (node (ref "ARDUINO_NANO3") (pin "2") (pinfunction "3V3_2") (pintype "output"))
      (node (ref "JP18") (pin "1") (pinfunction "1_1") (pintype "passive"))
    )
    (net (code "105") (name "Net-(ARDUINO_NANO3-A0)") (class "Default")
      (node (ref "ARDUINO_NANO3") (pin "4") (pinfunction "A0_4") (pintype "bidirectional"))
      (node (ref "JP17") (pin "8") (pinfunction "8_8") (pintype "passive"))
    )
    (net (code "106") (name "Net-(ARDUINO_NANO3-A1)") (class "Default")
      (node (ref "ARDUINO_NANO3") (pin "5") (pinfunction "A1_5") (pintype "bidirectional"))
      (node (ref "JP17") (pin "7") (pinfunction "7_7") (pintype "passive"))
    )
    (net (code "107") (name "Net-(ARDUINO_NANO3-A2)") (class "Default")
      (node (ref "ARDUINO_NANO3") (pin "6") (pinfunction "A2_6") (pintype "bidirectional"))
      (node (ref "JP17") (pin "6") (pinfunction "6_6") (pintype "passive"))
    )
    (net (code "108") (name "Net-(ARDUINO_NANO3-A3)") (class "Default")
      (node (ref "ARDUINO_NANO3") (pin "7") (pinfunction "A3_7") (pintype "bidirectional"))
      (node (ref "JP17") (pin "5") (pinfunction "5_5") (pintype "passive"))
    )
    (net (code "109") (name "Net-(ARDUINO_NANO3-A4)") (class "Default")
      (node (ref "ARDUINO_NANO3") (pin "8") (pinfunction "A4_8") (pintype "bidirectional"))
      (node (ref "JP17") (pin "4") (pinfunction "4_4") (pintype "passive"))
    )
    (net (code "110") (name "Net-(ARDUINO_NANO3-A5)") (class "Default")
      (node (ref "ARDUINO_NANO3") (pin "9") (pinfunction "A5_9") (pintype "bidirectional"))
      (node (ref "JP17") (pin "3") (pinfunction "3_3") (pintype "passive"))
    )
    (net (code "111") (name "Net-(ARDUINO_NANO3-A6)") (class "Default")
      (node (ref "ARDUINO_NANO3") (pin "10") (pinfunction "A6_10") (pintype "bidirectional"))
      (node (ref "JP17") (pin "2") (pinfunction "2_2") (pintype "passive"))
    )
    (net (code "112") (name "Net-(ARDUINO_NANO3-A7)") (class "Default")
      (node (ref "ARDUINO_NANO3") (pin "11") (pinfunction "A7_11") (pintype "bidirectional"))
      (node (ref "JP17") (pin "1") (pinfunction "1_1") (pintype "passive"))
    )
    (net (code "113") (name "Net-(ARDUINO_NANO3-D6)") (class "Default")
      (node (ref "ARDUINO_NANO3") (pin "24") (pinfunction "D6_24") (pintype "bidirectional"))
      (node (ref "JP19") (pin "3") (pinfunction "3_3") (pintype "passive"))
    )
    (net (code "114") (name "Net-(ARDUINO_NANO3-D7)") (class "Default")
      (node (ref "ARDUINO_NANO3") (pin "25") (pinfunction "D7_25") (pintype "bidirectional"))
      (node (ref "JP19") (pin "2") (pinfunction "2_2") (pintype "passive"))
    )
    (net (code "115") (name "Net-(ARDUINO_NANO3-D8)") (class "Default")
      (node (ref "ARDUINO_NANO3") (pin "26") (pinfunction "D8_26") (pintype "bidirectional"))
      (node (ref "JP19") (pin "1") (pinfunction "1_1") (pintype "passive"))
    )
    (net (code "116") (name "Net-(ARDUINO_NANO3-D13)") (class "Default")
      (node (ref "ARDUINO_NANO3") (pin "1") (pinfunction "D13_1") (pintype "bidirectional"))
      (node (ref "JP18") (pin "2") (pinfunction "2_2") (pintype "passive"))
    )
    (net (code "117") (name "Net-(LED1-C)") (class "Default")
      (node (ref "LED1") (pin "K") (pinfunction "C_K") (pintype "passive"))
      (node (ref "R3") (pin "2") (pinfunction "2_2") (pintype "passive"))
    )
    (net (code "118") (name "Net-(LED2-C)") (class "Default")
      (node (ref "LED2") (pin "K") (pinfunction "C_K") (pintype "passive"))
      (node (ref "R4") (pin "2") (pinfunction "2_2") (pintype "passive"))
    )
    (net (code "119") (name "Net-(LED3-C)") (class "Default")
      (node (ref "LED3") (pin "K") (pinfunction "C_K") (pintype "passive"))
      (node (ref "R1") (pin "2") (pinfunction "2_2") (pintype "passive"))
    )
    (net (code "120") (name "Net-(LED4-C)") (class "Default")
      (node (ref "LED4") (pin "K") (pinfunction "C_K") (pintype "passive"))
      (node (ref "R2") (pin "2") (pinfunction "2_2") (pintype "passive"))
    )
    (net (code "121") (name "unconnected-(ARDUINO_NANO1-AREF-Pad3)") (class "Default")
      (node (ref "ARDUINO_NANO1") (pin "3") (pinfunction "AREF_3") (pintype "input"))
    )
    (net (code "122") (name "unconnected-(ARDUINO_NANO1-~{RESET}-Pad13)") (class "Default")
      (node (ref "ARDUINO_NANO1") (pin "13") (pinfunction "~{RESET}_13") (pintype "input"))
    )
    (net (code "123") (name "unconnected-(ARDUINO_NANO1-~{RESET}-Pad18)") (class "Default")
      (node (ref "ARDUINO_NANO1") (pin "18") (pinfunction "~{RESET}_18") (pintype "input"))
    )
    (net (code "124") (name "unconnected-(ARDUINO_NANO2-AREF-Pad3)") (class "Default")
      (node (ref "ARDUINO_NANO2") (pin "3") (pinfunction "AREF_3") (pintype "input"))
    )
    (net (code "125") (name "unconnected-(ARDUINO_NANO2-~{RESET}-Pad13)") (class "Default")
      (node (ref "ARDUINO_NANO2") (pin "13") (pinfunction "~{RESET}_13") (pintype "input"))
    )
    (net (code "126") (name "unconnected-(ARDUINO_NANO2-~{RESET}-Pad18)") (class "Default")
      (node (ref "ARDUINO_NANO2") (pin "18") (pinfunction "~{RESET}_18") (pintype "input"))
    )
    (net (code "127") (name "unconnected-(ARDUINO_NANO3-AREF-Pad3)") (class "Default")
      (node (ref "ARDUINO_NANO3") (pin "3") (pinfunction "AREF_3") (pintype "input"))
    )
    (net (code "128") (name "unconnected-(ARDUINO_NANO3-~{RESET}-Pad13)") (class "Default")
      (node (ref "ARDUINO_NANO3") (pin "13") (pinfunction "~{RESET}_13") (pintype "input"))
    )
    (net (code "129") (name "unconnected-(ARDUINO_NANO3-~{RESET}-Pad18)") (class "Default")
      (node (ref "ARDUINO_NANO3") (pin "18") (pinfunction "~{RESET}_18") (pintype "input"))
    )
    (net (code "130") (name "unconnected-(X5-PadD+)") (class "Default")
      (node (ref "X5") (pin "D+") (pinfunction "D+_D+") (pintype "bidirectional"))
    )
    (net (code "131") (name "unconnected-(X5-PadD-)") (class "Default")
      (node (ref "X5") (pin "D-") (pinfunction "D-_D-") (pintype "bidirectional"))
    )
    (net (code "132") (name "unconnected-(X6-PadD+)") (class "Default")
      (node (ref "X6") (pin "D+") (pinfunction "D+_D+") (pintype "bidirectional"))
    )
    (net (code "133") (name "unconnected-(X6-PadD-)") (class "Default")
      (node (ref "X6") (pin "D-") (pinfunction "D-_D-") (pintype "bidirectional"))
    )
  )
)
